# DVT-Volga.net
KiCad netlist of a schematic drawn in Altium Designer
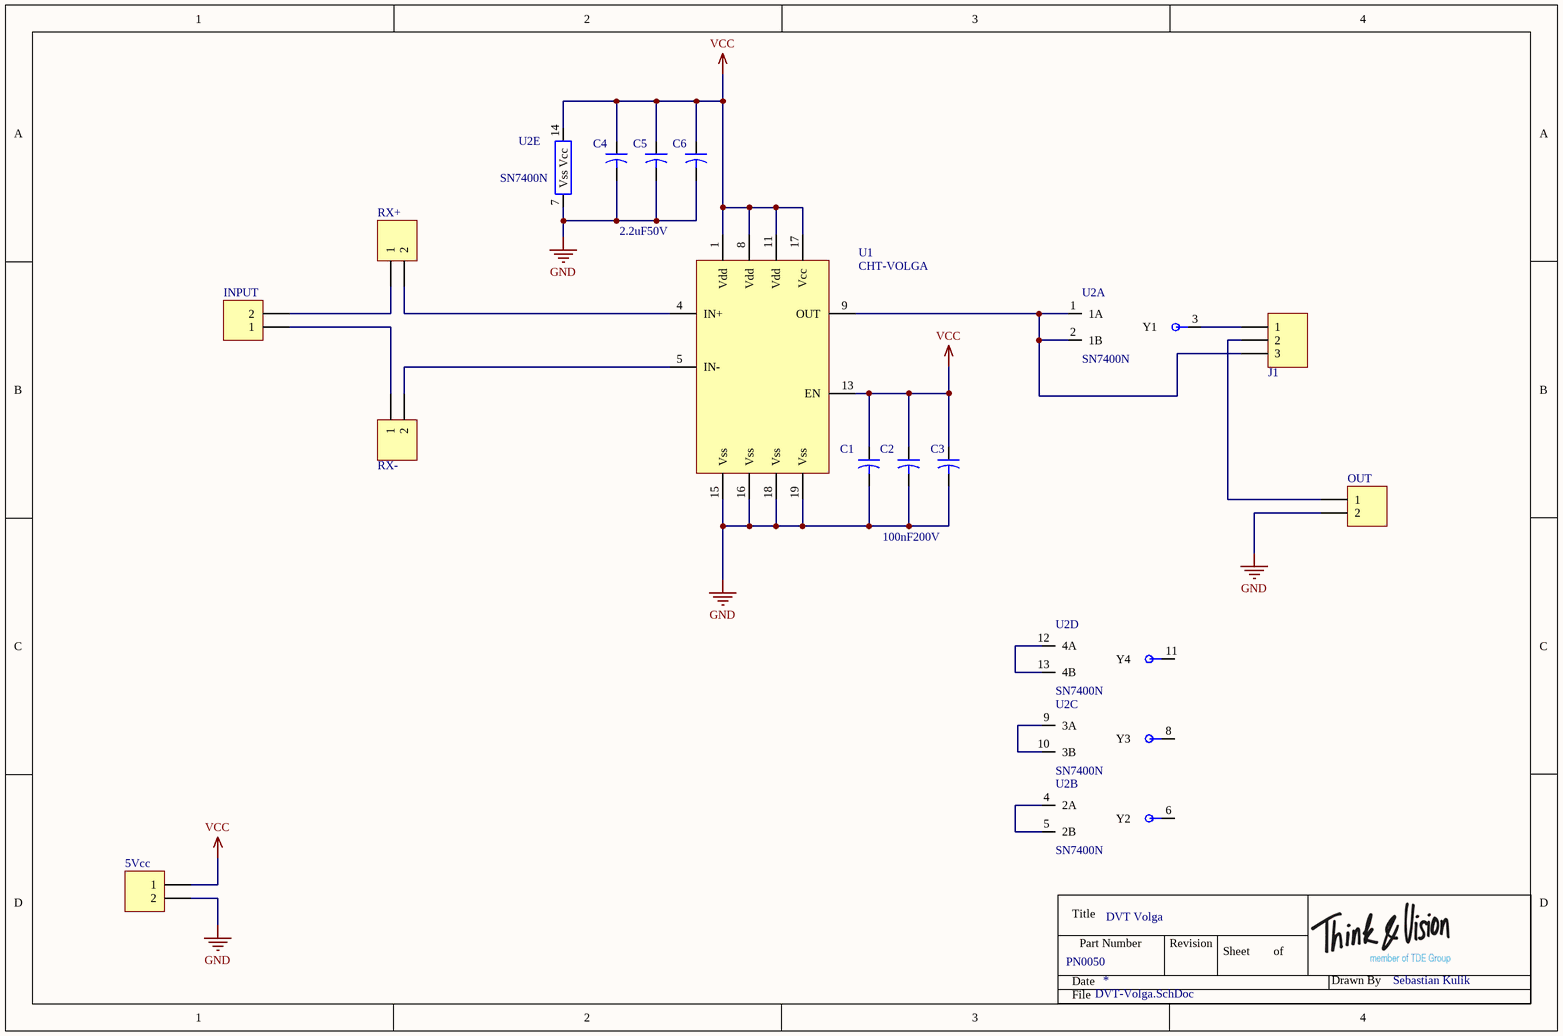
[diagram p0: DVT-Volga.SchDoc]

(export (version "E")
  (design (tool "Eeschema 10.0.6"))
  (components
    (comp (ref "5Vcc")
      (value "PHOENIX_1715721")
      (footprint "Phoenix-2-5_08")
      (description "Phoenix, 2 pol, 5.08mm, 22A, 715721")
      (fields (field (name "MANUFACTURER") "Phoenix") (field (name "PUBLISHER") "Sebastian Kulik"))
      (libsource (lib "") (part "2Pol_1715721_1"))
    )
    (comp (ref "C1")
      (value "100nF200V")
      (footprint "Dummy-10mm")
      (description "Capacitor-Dummy-THT")
      (fields (field (name "PUBLISHER") "Sebastian Kulik"))
      (libsource (lib "Capacitors") (part "Capacitor-Dummy-THT"))
    )
    (comp (ref "C2")
      (value "Capacitor-Dummy-THT")
      (footprint "Dummy-10mm")
      (fields (field (name "PUBLISHER") "Sebastian Kulik"))
      (libsource (lib "Capacitors") (part "Capacitor-Dummy-THT"))
    )
    (comp (ref "C3")
      (value "Capacitor-Dummy-THT")
      (footprint "Dummy-10mm")
      (fields (field (name "PUBLISHER") "Sebastian Kulik"))
      (libsource (lib "Capacitors") (part "Capacitor-Dummy-THT"))
    )
    (comp (ref "C4")
      (value "Capacitor-Dummy-THT")
      (footprint "Dummy-10mm")
      (fields (field (name "PUBLISHER") "Sebastian Kulik"))
      (libsource (lib "Capacitors") (part "Capacitor-Dummy-THT"))
    )
    (comp (ref "C5")
      (value "Capacitor-Dummy-THT")
      (footprint "Dummy-10mm")
      (fields (field (name "PUBLISHER") "Sebastian Kulik"))
      (libsource (lib "Capacitors") (part "Capacitor-Dummy-THT"))
    )
    (comp (ref "C6")
      (value "2.2uF50V")
      (footprint "Dummy-10mm")
      (description "Capacitor-Dummy-THT")
      (fields (field (name "PUBLISHER") "Sebastian Kulik"))
      (libsource (lib "Capacitors") (part "Capacitor-Dummy-THT"))
    )
    (comp (ref "INPUT")
      (value "PHOENIX_1715721")
      (footprint "Phoenix-2-5_08")
      (description "Phoenix, 2 pol, 5.08mm, 22A, 715721")
      (fields (field (name "MANUFACTURER") "Phoenix") (field (name "PUBLISHER") "Sebastian Kulik"))
      (libsource (lib "") (part "2Pol_1715721_2"))
    )
    (comp (ref "J1")
      (value "Header-3")
      (footprint "HDR1X3")
      (description "Header-3-Pin")
      (fields (field (name "PUBLISHER") "Sebastian Kulik"))
      (libsource (lib "Connectors") (part "Header-3"))
    )
    (comp (ref "OUT")
      (value "PHOENIX_1715721")
      (footprint "Phoenix-2-5_08")
      (description "Phoenix, 2 pol, 5.08mm, 22A, 715721")
      (fields (field (name "MANUFACTURER") "Phoenix") (field (name "PUBLISHER") "Sebastian Kulik"))
      (libsource (lib "Connectors") (part "2Pol_1715721"))
    )
    (comp (ref "RX+")
      (value "PHOENIX_1715721")
      (footprint "HDR1X2")
      (description "Header, 2-Pin")
      (fields (field (name "PUBLISHER") "Sebastian Kulik"))
      (libsource (lib "") (part "Header-2_1"))
    )
    (comp (ref "RX-")
      (value "PHOENIX_1715721")
      (footprint "HDR1X2")
      (description "Header, 2-Pin")
      (fields (field (name "PUBLISHER") "Sebastian Kulik"))
      (libsource (lib "Connectors") (part "Header-2"))
    )
    (comp (ref "U1")
      (value "CHT-VOLGA")
      (footprint "TDFP16")
      (description "Comparator, Hi-Temp, 25MHz")
      (fields (field (name "MANUFACTURER") "CISSOID") (field (name "PUBLISHER") "Sebastian Kulik"))
      (libsource (lib "ICs") (part "CHT-VOLGA"))
    )
    (comp (ref "U2")
      (value "SN7400N")
      (footprint "DIP-14")
      (description "Quad NAND, TTL")
      (fields (field (name "MANUFACTURER") "TI") (field (name "PUBLISHER") "Sebastian Kulik"))
      (libsource (lib "") (part "SN7400N_1"))
    )
  )
  (nets
    (net (code "1") (name "GND") (class "Default")
      (node (ref "5Vcc") (pin "2") (pinfunction "2_2") (pintype "passive"))
      (node (ref "C1") (pin "2") (pinfunction "2_2") (pintype "passive"))
      (node (ref "C2") (pin "2") (pinfunction "2_2") (pintype "passive"))
      (node (ref "C3") (pin "2") (pinfunction "2_2") (pintype "passive"))
      (node (ref "C4") (pin "2") (pinfunction "2_2") (pintype "passive"))
      (node (ref "C5") (pin "2") (pinfunction "2_2") (pintype "passive"))
      (node (ref "C6") (pin "2") (pinfunction "2_2") (pintype "passive"))
      (node (ref "OUT") (pin "2") (pinfunction "2_2") (pintype "passive"))
      (node (ref "U1") (pin "15") (pinfunction "Vss_15") (pintype "power_in"))
      (node (ref "U1") (pin "16") (pinfunction "Vss_16") (pintype "passive"))
      (node (ref "U1") (pin "18") (pinfunction "Vss_18") (pintype "power_in"))
      (node (ref "U1") (pin "19") (pinfunction "Vss_19") (pintype "power_in"))
      (node (ref "U2") (pin "7") (pinfunction "Vss_7") (pintype "passive"))
    )
    (net (code "2") (name "Net-(INPUT-Pad1)") (class "Default")
      (node (ref "INPUT") (pin "1") (pinfunction "1_1") (pintype "passive"))
      (node (ref "RX-") (pin "1") (pinfunction "1_1") (pintype "passive"))
    )
    (net (code "3") (name "Net-(INPUT-Pad2)") (class "Default")
      (node (ref "INPUT") (pin "2") (pinfunction "2_2") (pintype "passive"))
      (node (ref "RX+") (pin "1") (pinfunction "1_1") (pintype "passive"))
    )
    (net (code "4") (name "Net-(J1-Pad2)") (class "Default")
      (node (ref "J1") (pin "2") (pinfunction "2_2") (pintype "passive"))
      (node (ref "OUT") (pin "1") (pinfunction "1_1") (pintype "passive"))
    )
    (net (code "5") (name "Net-(U1-IN+)") (class "Default")
      (node (ref "RX+") (pin "2") (pinfunction "2_2") (pintype "passive"))
      (node (ref "U1") (pin "4") (pinfunction "IN+_4") (pintype "passive"))
    )
    (net (code "6") (name "Net-(U1-IN-)") (class "Default")
      (node (ref "RX-") (pin "2") (pinfunction "2_2") (pintype "passive"))
      (node (ref "U1") (pin "5") (pinfunction "IN-_5") (pintype "passive"))
    )
    (net (code "7") (name "Net-(U1-OUT)") (class "Default")
      (node (ref "J1") (pin "3") (pinfunction "3_3") (pintype "passive"))
      (node (ref "U1") (pin "9") (pinfunction "OUT_9") (pintype "power_in"))
      (node (ref "U2") (pin "1") (pinfunction "1A_1") (pintype "passive"))
      (node (ref "U2") (pin "2") (pinfunction "1B_2") (pintype "passive"))
    )
    (net (code "8") (name "Net-(U2A-Y1)") (class "Default")
      (node (ref "J1") (pin "1") (pinfunction "1_1") (pintype "passive"))
      (node (ref "U2") (pin "3") (pinfunction "Y1_3") (pintype "passive"))
    )
    (net (code "9") (name "Net-(U2B-2A)") (class "Default")
      (node (ref "U2") (pin "4") (pinfunction "2A_4") (pintype "passive"))
      (node (ref "U2") (pin "5") (pinfunction "2B_5") (pintype "passive"))
    )
    (net (code "10") (name "Net-(U2C-3A)") (class "Default")
      (node (ref "U2") (pin "10") (pinfunction "3B_10") (pintype "passive"))
      (node (ref "U2") (pin "9") (pinfunction "3A_9") (pintype "passive"))
    )
    (net (code "11") (name "Net-(U2D-4A)") (class "Default")
      (node (ref "U2") (pin "12") (pinfunction "4A_12") (pintype "passive"))
      (node (ref "U2") (pin "13") (pinfunction "4B_13") (pintype "passive"))
    )
    (net (code "12") (name "VCC") (class "Default")
      (node (ref "5Vcc") (pin "1") (pinfunction "1_1") (pintype "passive"))
      (node (ref "C1") (pin "1") (pinfunction "1_1") (pintype "passive"))
      (node (ref "C2") (pin "1") (pinfunction "1_1") (pintype "passive"))
      (node (ref "C3") (pin "1") (pinfunction "1_1") (pintype "passive"))
      (node (ref "C4") (pin "1") (pinfunction "1_1") (pintype "passive"))
      (node (ref "C5") (pin "1") (pinfunction "1_1") (pintype "passive"))
      (node (ref "C6") (pin "1") (pinfunction "1_1") (pintype "passive"))
      (node (ref "U1") (pin "1") (pinfunction "Vdd_1") (pintype "passive"))
      (node (ref "U1") (pin "11") (pinfunction "Vdd_11") (pintype "power_in"))
      (node (ref "U1") (pin "13") (pinfunction "EN_13") (pintype "passive"))
      (node (ref "U1") (pin "17") (pinfunction "Vcc_17") (pintype "passive"))
      (node (ref "U1") (pin "8") (pinfunction "Vdd_8") (pintype "power_in"))
      (node (ref "U2") (pin "14") (pinfunction "Vcc_14") (pintype "passive"))
    )
    (net (code "13") (name "unconnected-(U2B-Y2-Pad6)") (class "Default")
      (node (ref "U2") (pin "6") (pinfunction "Y2_6") (pintype "passive"))
    )
    (net (code "14") (name "unconnected-(U2C-Y3-Pad8)") (class "Default")
      (node (ref "U2") (pin "8") (pinfunction "Y3_8") (pintype "passive"))
    )
    (net (code "15") (name "unconnected-(U2D-Y4-Pad11)") (class "Default")
      (node (ref "U2") (pin "11") (pinfunction "Y4_11") (pintype "passive"))
    )
  )
)
